# AddBoardv2.net
KiCad netlist of a schematic drawn in EAGLE
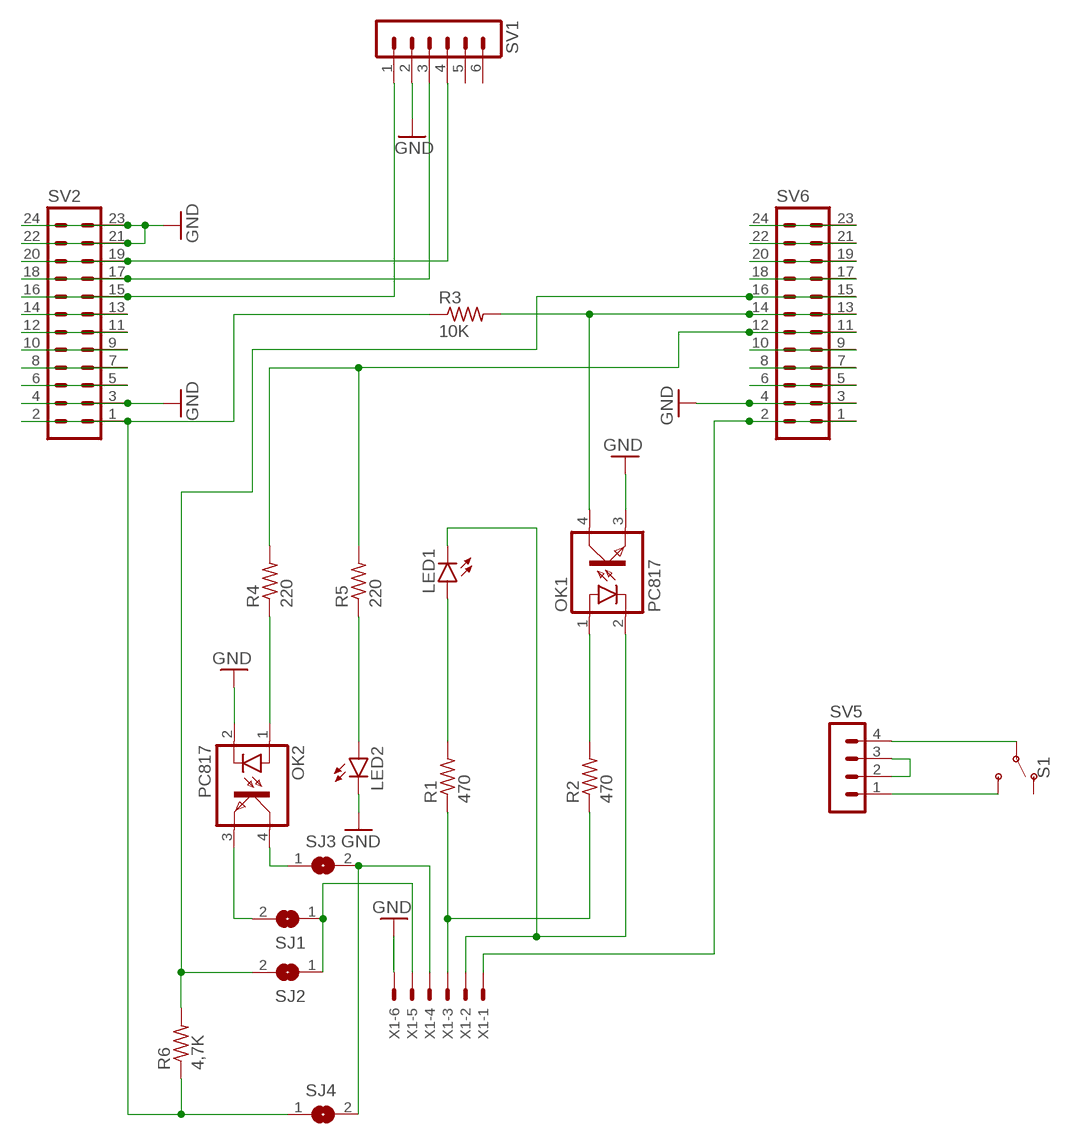
[diagram p0: schematic, sheet 1]

(export (version "E")
  (design (tool "Eeschema 10.0.6"))
  (components
    (comp (ref "LED1")
      (value "LEDCHIPLED_1206")
      (footprint "eagle-import:CHIPLED_1206")
      (libsource (lib "eagle-import") (part "LEDCHIPLED_1206"))
    )
    (comp (ref "LED2")
      (value "LEDCHIPLED_1206")
      (footprint "eagle-import:CHIPLED_1206")
      (libsource (lib "eagle-import") (part "LEDCHIPLED_1206"))
    )
    (comp (ref "OK1")
      (value "PC817")
      (footprint "eagle-import:DIL04")
      (fields (field (name "MPN") "PC817X4J000F"))
      (libsource (lib "eagle-import") (part "PC817"))
    )
    (comp (ref "OK2")
      (value "PC817")
      (footprint "eagle-import:DIL04")
      (fields (field (name "MPN") "PC817X4J000F"))
      (libsource (lib "eagle-import") (part "PC817"))
    )
    (comp (ref "R1")
      (value "470")
      (footprint "eagle-import:RES_1206")
      (fields
        (field (name "DIGIKEY_PART_NUMBER") "P0.0ETR-ND")
        (field (name "MANUFACTURER") "Panasonic Electronic Components")
        (field (name "MPN") "ERJ-8GEY0R00V")
        (field (name "CREATED_BY") "PCBLayout.com")
      )
      (libsource (lib "eagle-import") (part "ERJ-8GEY0R00V"))
    )
    (comp (ref "R2")
      (value "470")
      (footprint "eagle-import:RES_1206")
      (fields
        (field (name "DIGIKEY_PART_NUMBER") "P0.0ETR-ND")
        (field (name "MANUFACTURER") "Panasonic Electronic Components")
        (field (name "MPN") "ERJ-8GEY0R00V")
        (field (name "CREATED_BY") "PCBLayout.com")
      )
      (libsource (lib "eagle-import") (part "ERJ-8GEY0R00V"))
    )
    (comp (ref "R3")
      (value "10K")
      (footprint "eagle-import:RES_1206")
      (fields
        (field (name "DIGIKEY_PART_NUMBER") "P0.0ETR-ND")
        (field (name "MANUFACTURER") "Panasonic Electronic Components")
        (field (name "MPN") "ERJ-8GEY0R00V")
        (field (name "CREATED_BY") "PCBLayout.com")
      )
      (libsource (lib "eagle-import") (part "ERJ-8GEY0R00V"))
    )
    (comp (ref "R4")
      (value "220")
      (footprint "eagle-import:RES_1206")
      (fields
        (field (name "DIGIKEY_PART_NUMBER") "P0.0ETR-ND")
        (field (name "MANUFACTURER") "Panasonic Electronic Components")
        (field (name "MPN") "ERJ-8GEY0R00V")
        (field (name "CREATED_BY") "PCBLayout.com")
      )
      (libsource (lib "eagle-import") (part "ERJ-8GEY0R00V"))
    )
    (comp (ref "R5")
      (value "220")
      (footprint "eagle-import:RES_1206")
      (fields
        (field (name "DIGIKEY_PART_NUMBER") "P0.0ETR-ND")
        (field (name "MANUFACTURER") "Panasonic Electronic Components")
        (field (name "MPN") "ERJ-8GEY0R00V")
        (field (name "CREATED_BY") "PCBLayout.com")
      )
      (libsource (lib "eagle-import") (part "ERJ-8GEY0R00V"))
    )
    (comp (ref "R6")
      (value "4,7K")
      (footprint "eagle-import:RES_1206")
      (fields
        (field (name "DIGIKEY_PART_NUMBER") "WSLP-.05TR-ND")
        (field (name "MANUFACTURER") "Vishay Dale")
        (field (name "MPN") "WSLP1206R0500FEA")
        (field (name "CREATED_BY") "PCBLayout.com")
      )
      (libsource (lib "eagle-import") (part "WSLP1206R0500FEA"))
    )
    (comp (ref "S1")
      (value "SWITCH-SPDT-SMD-RIGHT-ANGLE")
      (footprint "eagle-import:SWITCH_SPST_SMD_A")
      (libsource (lib "eagle-import") (part "SWITCH-SPDT-SMD-RIGHT-ANGLE"))
    )
    (comp (ref "SJ1") (value "SJ") (footprint "eagle-import:SJ") (libsource (lib "eagle-import") (part "SJ")))
    (comp (ref "SJ2") (value "SJ") (footprint "eagle-import:SJ") (libsource (lib "eagle-import") (part "SJ")))
    (comp (ref "SJ3") (value "SJ") (footprint "eagle-import:SJ") (libsource (lib "eagle-import") (part "SJ")))
    (comp (ref "SJ4") (value "SJ") (footprint "eagle-import:SJ") (libsource (lib "eagle-import") (part "SJ")))
    (comp (ref "SV1")
      (value "MA06-1")
      (footprint "eagle-import:MA06-1")
      (libsource (lib "eagle-import") (part "MA06-1"))
    )
    (comp (ref "SV2")
      (value "MA12-2")
      (footprint "eagle-import:MA12-2")
      (libsource (lib "eagle-import") (part "MA12-2"))
    )
    (comp (ref "SV5")
      (value "MA04-1")
      (footprint "eagle-import:MA04-1")
      (libsource (lib "eagle-import") (part "MA04-1"))
    )
    (comp (ref "SV6")
      (value "MA12-2")
      (footprint "eagle-import:MA12-2")
      (libsource (lib "eagle-import") (part "MA12-2"))
    )
    (comp (ref "X1")
      (value "22-23-2061")
      (footprint "eagle-import:22-23-2061")
      (fields (field (name "MF") "MOLEX"))
      (libsource (lib "eagle-import") (part "22-23-2061"))
    )
  )
  (nets
    (net (code "1") (name "GND") (class "Default")
      (node (ref "LED2") (pin "C") (pinfunction "C_C") (pintype "passive"))
      (node (ref "OK1") (pin "3") (pinfunction "EMIT_3") (pintype "passive"))
      (node (ref "OK2") (pin "2") (pinfunction "C_2") (pintype "passive"))
      (node (ref "SV1") (pin "2") (pinfunction "2_2") (pintype "passive"))
      (node (ref "SV2") (pin "21") (pinfunction "21_21") (pintype "passive"))
      (node (ref "SV2") (pin "22") (pinfunction "22_22") (pintype "passive"))
      (node (ref "SV2") (pin "23") (pinfunction "23_23") (pintype "passive"))
      (node (ref "SV2") (pin "24") (pinfunction "24_24") (pintype "passive"))
      (node (ref "SV2") (pin "3") (pinfunction "3_3") (pintype "passive"))
      (node (ref "SV2") (pin "4") (pinfunction "4_4") (pintype "passive"))
      (node (ref "SV6") (pin "3") (pinfunction "3_3") (pintype "passive"))
      (node (ref "SV6") (pin "4") (pinfunction "4_4") (pintype "passive"))
      (node (ref "X1") (pin "6") (pinfunction "S_6") (pintype "passive"))
    )
    (net (code "2") (name "Net-(LED1-PadA)") (class "Default")
      (node (ref "LED1") (pin "A") (pinfunction "A_A") (pintype "passive"))
      (node (ref "R1") (pin "2") (pinfunction "2_2") (pintype "passive"))
    )
    (net (code "3") (name "Net-(LED2-PadA)") (class "Default")
      (node (ref "LED2") (pin "A") (pinfunction "A_A") (pintype "passive"))
      (node (ref "R5") (pin "1") (pinfunction "1_1") (pintype "passive"))
    )
    (net (code "4") (name "Net-(OK1-A)") (class "Default")
      (node (ref "OK1") (pin "1") (pinfunction "A_1") (pintype "passive"))
      (node (ref "R2") (pin "2") (pinfunction "2_2") (pintype "passive"))
    )
    (net (code "5") (name "Net-(OK1-C)") (class "Default")
      (node (ref "LED1") (pin "C") (pinfunction "C_C") (pintype "passive"))
      (node (ref "OK1") (pin "2") (pinfunction "C_2") (pintype "passive"))
      (node (ref "X1") (pin "2") (pinfunction "S_2") (pintype "passive"))
    )
    (net (code "6") (name "Net-(OK1-COL)") (class "Default")
      (node (ref "OK1") (pin "4") (pinfunction "COL_4") (pintype "passive"))
      (node (ref "R3") (pin "2") (pinfunction "2_2") (pintype "passive"))
      (node (ref "SV6") (pin "13") (pinfunction "13_13") (pintype "passive"))
      (node (ref "SV6") (pin "14") (pinfunction "14_14") (pintype "passive"))
    )
    (net (code "7") (name "Net-(OK2-A)") (class "Default")
      (node (ref "OK2") (pin "1") (pinfunction "A_1") (pintype "passive"))
      (node (ref "R4") (pin "1") (pinfunction "1_1") (pintype "passive"))
    )
    (net (code "8") (name "Net-(OK2-COL)") (class "Default")
      (node (ref "OK2") (pin "4") (pinfunction "COL_4") (pintype "passive"))
      (node (ref "SJ3") (pin "1") (pinfunction "1_1") (pintype "passive"))
    )
    (net (code "9") (name "Net-(OK2-EMIT)") (class "Default")
      (node (ref "OK2") (pin "3") (pinfunction "EMIT_3") (pintype "passive"))
      (node (ref "SJ1") (pin "2") (pinfunction "2_2") (pintype "passive"))
    )
    (net (code "10") (name "Net-(R3-Pad1)") (class "Default")
      (node (ref "R3") (pin "1") (pinfunction "1_1") (pintype "passive"))
      (node (ref "R6") (pin "1") (pinfunction "1_1") (pintype "passive"))
      (node (ref "SJ4") (pin "1") (pinfunction "1_1") (pintype "passive"))
      (node (ref "SV2") (pin "1") (pinfunction "1_1") (pintype "passive"))
      (node (ref "SV2") (pin "2") (pinfunction "2_2") (pintype "passive"))
    )
    (net (code "11") (name "Net-(R4-Pad2)") (class "Default")
      (node (ref "R4") (pin "2") (pinfunction "2_2") (pintype "passive"))
      (node (ref "R5") (pin "2") (pinfunction "2_2") (pintype "passive"))
      (node (ref "SV6") (pin "11") (pinfunction "11_11") (pintype "passive"))
      (node (ref "SV6") (pin "12") (pinfunction "12_12") (pintype "passive"))
    )
    (net (code "12") (name "Net-(R6-Pad2)") (class "Default")
      (node (ref "R6") (pin "2") (pinfunction "2_2") (pintype "passive"))
      (node (ref "SJ2") (pin "2") (pinfunction "2_2") (pintype "passive"))
      (node (ref "SV6") (pin "15") (pinfunction "15_15") (pintype "passive"))
      (node (ref "SV6") (pin "16") (pinfunction "16_16") (pintype "passive"))
    )
    (net (code "13") (name "Net-(S1-P)") (class "Default")
      (node (ref "S1") (pin "2") (pinfunction "P_2") (pintype "passive"))
      (node (ref "SV5") (pin "4") (pinfunction "4_4") (pintype "passive"))
    )
    (net (code "14") (name "Net-(S1-S)") (class "Default")
      (node (ref "S1") (pin "3") (pinfunction "S_3") (pintype "passive"))
      (node (ref "SV5") (pin "1") (pinfunction "1_1") (pintype "passive"))
    )
    (net (code "15") (name "Net-(SV1-Pad1)") (class "Default")
      (node (ref "SV1") (pin "1") (pinfunction "1_1") (pintype "passive"))
      (node (ref "SV2") (pin "15") (pinfunction "15_15") (pintype "passive"))
      (node (ref "SV2") (pin "16") (pinfunction "16_16") (pintype "passive"))
    )
    (net (code "16") (name "Net-(SV1-Pad3)") (class "Default")
      (node (ref "SV1") (pin "3") (pinfunction "3_3") (pintype "passive"))
      (node (ref "SV2") (pin "17") (pinfunction "17_17") (pintype "passive"))
      (node (ref "SV2") (pin "18") (pinfunction "18_18") (pintype "passive"))
    )
    (net (code "17") (name "Net-(SV1-Pad4)") (class "Default")
      (node (ref "SV1") (pin "4") (pinfunction "4_4") (pintype "passive"))
      (node (ref "SV2") (pin "19") (pinfunction "19_19") (pintype "passive"))
      (node (ref "SV2") (pin "20") (pinfunction "20_20") (pintype "passive"))
    )
    (net (code "18") (name "Net-(SV2-Pad5)") (class "Default")
      (node (ref "SV2") (pin "5") (pinfunction "5_5") (pintype "passive"))
      (node (ref "SV2") (pin "6") (pinfunction "6_6") (pintype "passive"))
    )
    (net (code "19") (name "Net-(SV2-Pad7)") (class "Default")
      (node (ref "SV2") (pin "7") (pinfunction "7_7") (pintype "passive"))
      (node (ref "SV2") (pin "8") (pinfunction "8_8") (pintype "passive"))
    )
    (net (code "20") (name "Net-(SV2-Pad10)") (class "Default")
      (node (ref "SV2") (pin "10") (pinfunction "10_10") (pintype "passive"))
      (node (ref "SV2") (pin "9") (pinfunction "9_9") (pintype "passive"))
    )
    (net (code "21") (name "Net-(SV2-Pad11)") (class "Default")
      (node (ref "SV2") (pin "11") (pinfunction "11_11") (pintype "passive"))
      (node (ref "SV2") (pin "12") (pinfunction "12_12") (pintype "passive"))
    )
    (net (code "22") (name "Net-(SV2-Pad13)") (class "Default")
      (node (ref "SV2") (pin "13") (pinfunction "13_13") (pintype "passive"))
      (node (ref "SV2") (pin "14") (pinfunction "14_14") (pintype "passive"))
    )
    (net (code "23") (name "Net-(SV5-Pad2)") (class "Default")
      (node (ref "SV5") (pin "2") (pinfunction "2_2") (pintype "passive"))
      (node (ref "SV5") (pin "3") (pinfunction "3_3") (pintype "passive"))
    )
    (net (code "24") (name "Net-(SV6-Pad5)") (class "Default")
      (node (ref "SV6") (pin "5") (pinfunction "5_5") (pintype "passive"))
      (node (ref "SV6") (pin "6") (pinfunction "6_6") (pintype "passive"))
    )
    (net (code "25") (name "Net-(SV6-Pad7)") (class "Default")
      (node (ref "SV6") (pin "7") (pinfunction "7_7") (pintype "passive"))
      (node (ref "SV6") (pin "8") (pinfunction "8_8") (pintype "passive"))
    )
    (net (code "26") (name "Net-(SV6-Pad10)") (class "Default")
      (node (ref "SV6") (pin "10") (pinfunction "10_10") (pintype "passive"))
      (node (ref "SV6") (pin "9") (pinfunction "9_9") (pintype "passive"))
    )
    (net (code "27") (name "Net-(SV6-Pad17)") (class "Default")
      (node (ref "SV6") (pin "17") (pinfunction "17_17") (pintype "passive"))
      (node (ref "SV6") (pin "18") (pinfunction "18_18") (pintype "passive"))
    )
    (net (code "28") (name "Net-(SV6-Pad19)") (class "Default")
      (node (ref "SV6") (pin "19") (pinfunction "19_19") (pintype "passive"))
      (node (ref "SV6") (pin "20") (pinfunction "20_20") (pintype "passive"))
    )
    (net (code "29") (name "Net-(SV6-Pad21)") (class "Default")
      (node (ref "SV6") (pin "21") (pinfunction "21_21") (pintype "passive"))
      (node (ref "SV6") (pin "22") (pinfunction "22_22") (pintype "passive"))
    )
    (net (code "30") (name "Net-(SV6-Pad23)") (class "Default")
      (node (ref "SV6") (pin "23") (pinfunction "23_23") (pintype "passive"))
      (node (ref "SV6") (pin "24") (pinfunction "24_24") (pintype "passive"))
    )
    (net (code "31") (name "Net-(X1A-S)") (class "Default")
      (node (ref "SV6") (pin "1") (pinfunction "1_1") (pintype "passive"))
      (node (ref "SV6") (pin "2") (pinfunction "2_2") (pintype "passive"))
      (node (ref "X1") (pin "1") (pinfunction "S_1") (pintype "passive"))
    )
    (net (code "32") (name "Net-(X1C-S)") (class "Default")
      (node (ref "R1") (pin "1") (pinfunction "1_1") (pintype "passive"))
      (node (ref "R2") (pin "1") (pinfunction "1_1") (pintype "passive"))
      (node (ref "X1") (pin "3") (pinfunction "S_3") (pintype "passive"))
    )
    (net (code "33") (name "Net-(X1D-S)") (class "Default")
      (node (ref "SJ3") (pin "2") (pinfunction "2_2") (pintype "passive"))
      (node (ref "SJ4") (pin "2") (pinfunction "2_2") (pintype "passive"))
      (node (ref "X1") (pin "4") (pinfunction "S_4") (pintype "passive"))
    )
    (net (code "34") (name "Net-(X1E-S)") (class "Default")
      (node (ref "SJ1") (pin "1") (pinfunction "1_1") (pintype "passive"))
      (node (ref "SJ2") (pin "1") (pinfunction "1_1") (pintype "passive"))
      (node (ref "X1") (pin "5") (pinfunction "S_5") (pintype "passive"))
    )
    (net (code "35") (name "unconnected-(S1-O-Pad1)") (class "Default")
      (node (ref "S1") (pin "1") (pinfunction "O_1") (pintype "passive"))
    )
    (net (code "36") (name "unconnected-(SV1-Pad5)") (class "Default")
      (node (ref "SV1") (pin "5") (pinfunction "5_5") (pintype "passive"))
    )
    (net (code "37") (name "unconnected-(SV1-Pad6)") (class "Default")
      (node (ref "SV1") (pin "6") (pinfunction "6_6") (pintype "passive"))
    )
  )
)
